# LED7seg.net
KiCad netlist of a schematic drawn in Altium Designer
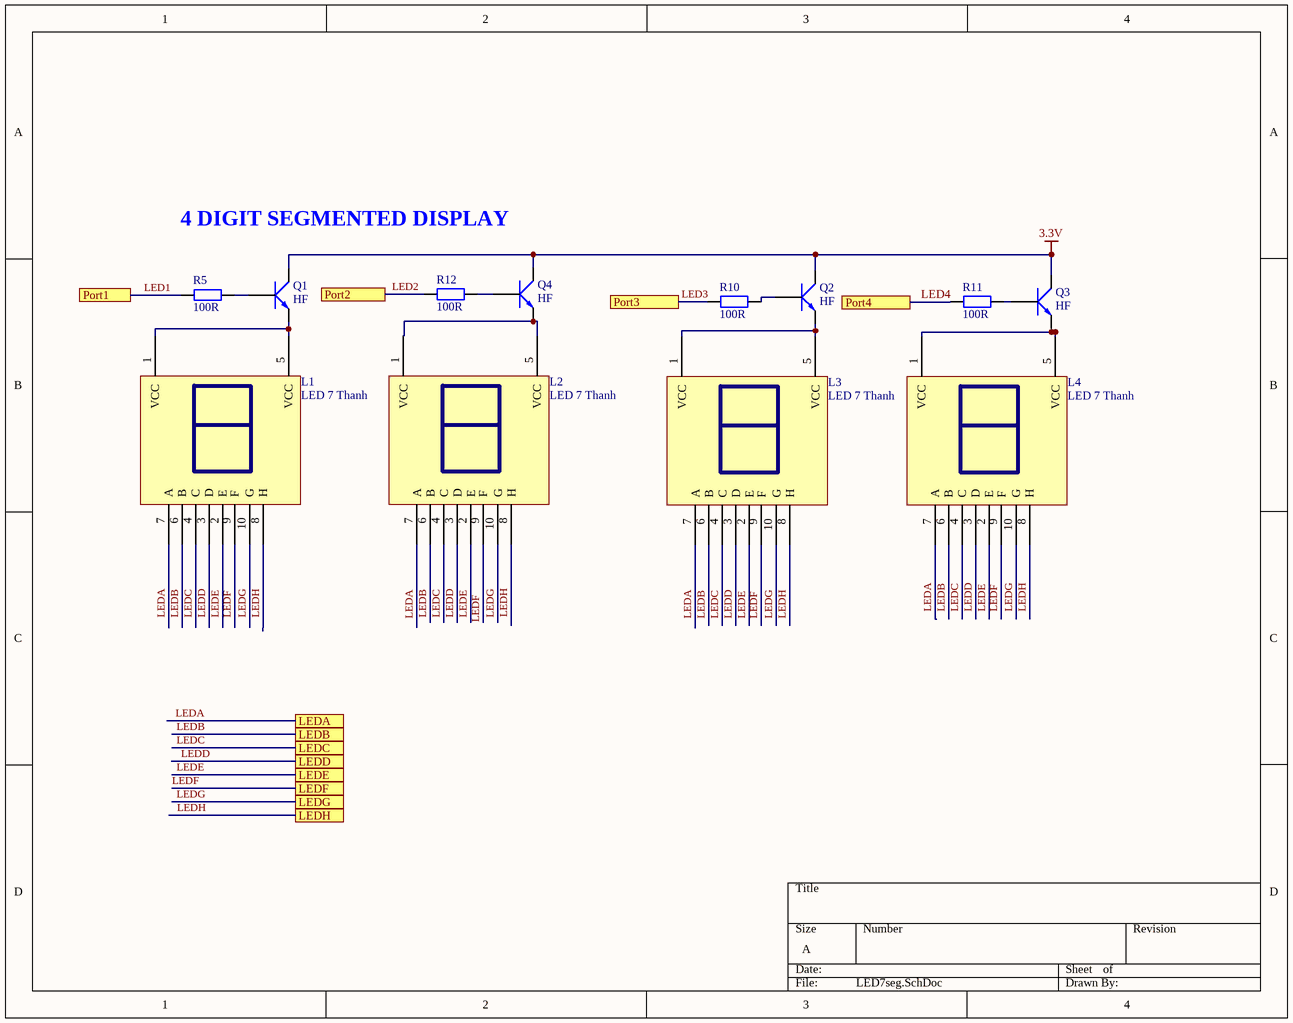
[diagram p0: LED7seg.SchDoc]

(export (version "E")
  (design (tool "Eeschema 10.0.6"))
  (components
    (comp (ref "L1")
      (value "LED 7 Thanh")
      (footprint "LED7SEG_2.3inch")
      (description "Dán")
      (libsource (lib "Altium_Lib_by_KhueNguyenCreator") (part "LED 7x1 2.3inch Anot"))
    )
    (comp (ref "L2")
      (value "LED 7 Thanh")
      (footprint "LED7SEG_2.3inch")
      (description "Dán")
      (libsource (lib "Altium_Lib_by_KhueNguyenCreator") (part "LED 7x1 2.3inch Anot"))
    )
    (comp (ref "L3")
      (value "LED 7 Thanh")
      (footprint "LED7SEG_2.3inch")
      (description "Dán")
      (libsource (lib "Altium_Lib_by_KhueNguyenCreator") (part "LED 7x1 2.3inch Anot"))
    )
    (comp (ref "L4")
      (value "LED 7 Thanh")
      (footprint "LED7SEG_2.3inch")
      (description "Dán")
      (libsource (lib "Altium_Lib_by_KhueNguyenCreator") (part "LED 7x1 2.3inch Anot"))
    )
    (comp (ref "Q1")
      (value "HF")
      (footprint "SOT23")
      (description "NPN transistor")
      (libsource (lib "Altium_Lib_by_KhueNguyenCreator") (part "C1815 HF SMD"))
    )
    (comp (ref "Q2")
      (value "HF")
      (footprint "SOT23")
      (description "NPN transistor")
      (libsource (lib "Altium_Lib_by_KhueNguyenCreator") (part "C1815 HF SMD"))
    )
    (comp (ref "Q3")
      (value "HF")
      (footprint "SOT23")
      (description "NPN transistor")
      (libsource (lib "Altium_Lib_by_KhueNguyenCreator") (part "C1815 HF SMD"))
    )
    (comp (ref "Q4")
      (value "HF")
      (footprint "SOT23")
      (description "NPN transistor")
      (libsource (lib "Altium_Lib_by_KhueNguyenCreator") (part "C1815 HF SMD"))
    )
    (comp (ref "R5")
      (value "100R")
      (footprint "tro smd 0805")
      (description "Dán")
      (libsource (lib "Altium_Lib_by_KhueNguyenCreator") (part "Tro 0805 5% 100R"))
    )
    (comp (ref "R10")
      (value "100R")
      (footprint "tro smd 0805")
      (description "Dán")
      (libsource (lib "Altium_Lib_by_KhueNguyenCreator") (part "Tro 0805 5% 100R"))
    )
    (comp (ref "R11")
      (value "100R")
      (footprint "tro smd 0805")
      (description "Dán")
      (libsource (lib "Altium_Lib_by_KhueNguyenCreator") (part "Tro 0805 5% 100R"))
    )
    (comp (ref "R12")
      (value "100R")
      (footprint "tro smd 0805")
      (description "Dán")
      (libsource (lib "Altium_Lib_by_KhueNguyenCreator") (part "Tro 0805 5% 100R"))
    )
  )
  (nets
    (net (code "1") (name "/LED1") (class "Default")
      (node (ref "R5") (pin "1") (pinfunction "1_1") (pintype "passive"))
    )
    (net (code "2") (name "/LED2") (class "Default")
      (node (ref "R12") (pin "1") (pinfunction "1_1") (pintype "passive"))
    )
    (net (code "3") (name "/LED3") (class "Default")
      (node (ref "R10") (pin "1") (pinfunction "1_1") (pintype "passive"))
    )
    (net (code "4") (name "/LED4") (class "Default")
      (node (ref "R11") (pin "1") (pinfunction "1_1") (pintype "passive"))
    )
    (net (code "5") (name "/LEDA") (class "Default")
      (node (ref "L1") (pin "7") (pinfunction "A_7") (pintype "passive"))
      (node (ref "L2") (pin "7") (pinfunction "A_7") (pintype "passive"))
      (node (ref "L3") (pin "7") (pinfunction "A_7") (pintype "passive"))
      (node (ref "L4") (pin "7") (pinfunction "A_7") (pintype "passive"))
    )
    (net (code "6") (name "/LEDB") (class "Default")
      (node (ref "L1") (pin "6") (pinfunction "B_6") (pintype "passive"))
      (node (ref "L2") (pin "6") (pinfunction "B_6") (pintype "passive"))
      (node (ref "L3") (pin "6") (pinfunction "B_6") (pintype "passive"))
      (node (ref "L4") (pin "6") (pinfunction "B_6") (pintype "passive"))
    )
    (net (code "7") (name "/LEDC") (class "Default")
      (node (ref "L1") (pin "4") (pinfunction "C_4") (pintype "passive"))
      (node (ref "L2") (pin "4") (pinfunction "C_4") (pintype "passive"))
      (node (ref "L3") (pin "4") (pinfunction "C_4") (pintype "passive"))
      (node (ref "L4") (pin "4") (pinfunction "C_4") (pintype "passive"))
    )
    (net (code "8") (name "/LEDD") (class "Default")
      (node (ref "L1") (pin "3") (pinfunction "D_3") (pintype "passive"))
      (node (ref "L2") (pin "3") (pinfunction "D_3") (pintype "passive"))
      (node (ref "L3") (pin "3") (pinfunction "D_3") (pintype "passive"))
      (node (ref "L4") (pin "3") (pinfunction "D_3") (pintype "passive"))
    )
    (net (code "9") (name "/LEDE") (class "Default")
      (node (ref "L1") (pin "2") (pinfunction "E_2") (pintype "passive"))
      (node (ref "L2") (pin "2") (pinfunction "E_2") (pintype "passive"))
      (node (ref "L3") (pin "2") (pinfunction "E_2") (pintype "passive"))
      (node (ref "L4") (pin "2") (pinfunction "E_2") (pintype "passive"))
    )
    (net (code "10") (name "/LEDF") (class "Default")
      (node (ref "L1") (pin "9") (pinfunction "F_9") (pintype "passive"))
      (node (ref "L2") (pin "9") (pinfunction "F_9") (pintype "passive"))
      (node (ref "L3") (pin "9") (pinfunction "F_9") (pintype "passive"))
      (node (ref "L4") (pin "9") (pinfunction "F_9") (pintype "passive"))
    )
    (net (code "11") (name "/LEDG") (class "Default")
      (node (ref "L1") (pin "10") (pinfunction "G_10") (pintype "passive"))
      (node (ref "L2") (pin "10") (pinfunction "G_10") (pintype "passive"))
      (node (ref "L3") (pin "10") (pinfunction "G_10") (pintype "passive"))
      (node (ref "L4") (pin "10") (pinfunction "G_10") (pintype "passive"))
    )
    (net (code "12") (name "/LEDH") (class "Default")
      (node (ref "L1") (pin "8") (pinfunction "H_8") (pintype "passive"))
      (node (ref "L2") (pin "8") (pinfunction "H_8") (pintype "passive"))
      (node (ref "L3") (pin "8") (pinfunction "H_8") (pintype "passive"))
      (node (ref "L4") (pin "8") (pinfunction "H_8") (pintype "passive"))
    )
    (net (code "13") (name "3.3V") (class "Default")
      (node (ref "Q1") (pin "3") (pinfunction "C_3") (pintype "passive"))
      (node (ref "Q2") (pin "3") (pinfunction "C_3") (pintype "passive"))
      (node (ref "Q3") (pin "3") (pinfunction "C_3") (pintype "passive"))
      (node (ref "Q4") (pin "3") (pinfunction "C_3") (pintype "passive"))
    )
    (net (code "14") (name "Net-(Q1-B)") (class "Default")
      (node (ref "Q1") (pin "1") (pinfunction "B_1") (pintype "passive"))
      (node (ref "R5") (pin "2") (pinfunction "2_2") (pintype "passive"))
    )
    (net (code "15") (name "Net-(Q1-E)") (class "Default")
      (node (ref "L1") (pin "1") (pinfunction "VCC_1") (pintype "passive"))
      (node (ref "L1") (pin "5") (pinfunction "VCC_5") (pintype "passive"))
      (node (ref "Q1") (pin "2") (pinfunction "E_2") (pintype "passive"))
    )
    (net (code "16") (name "Net-(Q2-B)") (class "Default")
      (node (ref "Q2") (pin "1") (pinfunction "B_1") (pintype "passive"))
      (node (ref "R10") (pin "2") (pinfunction "2_2") (pintype "passive"))
    )
    (net (code "17") (name "Net-(Q2-E)") (class "Default")
      (node (ref "L3") (pin "1") (pinfunction "VCC_1") (pintype "passive"))
      (node (ref "L3") (pin "5") (pinfunction "VCC_5") (pintype "passive"))
      (node (ref "Q2") (pin "2") (pinfunction "E_2") (pintype "passive"))
    )
    (net (code "18") (name "Net-(Q3-B)") (class "Default")
      (node (ref "Q3") (pin "1") (pinfunction "B_1") (pintype "passive"))
      (node (ref "R11") (pin "2") (pinfunction "2_2") (pintype "passive"))
    )
    (net (code "19") (name "Net-(Q3-E)") (class "Default")
      (node (ref "L4") (pin "1") (pinfunction "VCC_1") (pintype "passive"))
      (node (ref "L4") (pin "5") (pinfunction "VCC_5") (pintype "passive"))
      (node (ref "Q3") (pin "2") (pinfunction "E_2") (pintype "passive"))
    )
    (net (code "20") (name "Net-(Q4-B)") (class "Default")
      (node (ref "Q4") (pin "1") (pinfunction "B_1") (pintype "passive"))
      (node (ref "R12") (pin "2") (pinfunction "2_2") (pintype "passive"))
    )
    (net (code "21") (name "Net-(Q4-E)") (class "Default")
      (node (ref "L2") (pin "1") (pinfunction "VCC_1") (pintype "passive"))
      (node (ref "L2") (pin "5") (pinfunction "VCC_5") (pintype "passive"))
      (node (ref "Q4") (pin "2") (pinfunction "E_2") (pintype "passive"))
    )
  )
)
